# FPGA_MEMORIES.net
KiCad netlist of a schematic drawn in Altium Designer
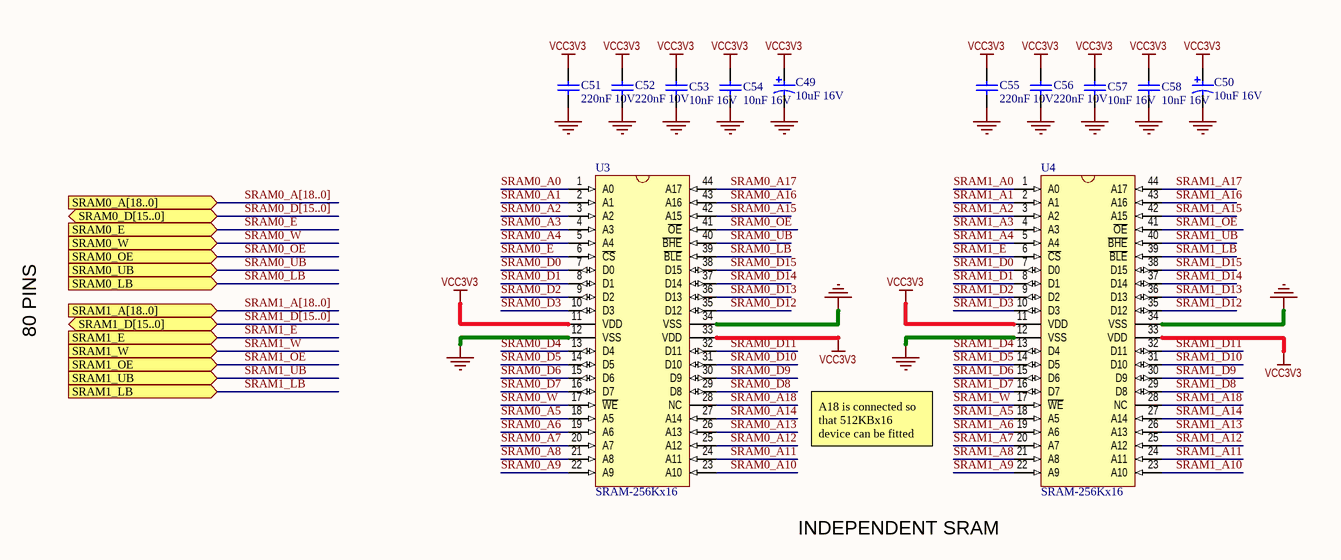
[diagram p0: FPGA_MEMORIES.SchDoc]

(export (version "E")
  (design (tool "Eeschema 10.0.6"))
  (components
    (comp (ref "C49")
      (value "10uF 16V")
      (footprint "CAPC3528")
      (description "Polar Capacitor")
      (libsource (lib "Altium Design Library") (part "CAP-P"))
    )
    (comp (ref "C50")
      (value "10uF 16V")
      (footprint "CAPC3528")
      (description "Polar Capacitor")
      (libsource (lib "Altium Design Library") (part "CAP-P"))
    )
    (comp (ref "C51")
      (value "220nF 10V")
      (footprint "CAPC1608")
      (description "Capacitor")
      (libsource (lib "Altium Design Library") (part "CAP-NP"))
    )
    (comp (ref "C52")
      (value "220nF 10V")
      (footprint "CAPC1608")
      (description "Capacitor")
      (libsource (lib "Altium Design Library") (part "CAP-NP"))
    )
    (comp (ref "C53")
      (value "10nF 16V")
      (footprint "CAPC1005")
      (description "Capacitor")
      (libsource (lib "Altium Design Library") (part "CAP-NP"))
    )
    (comp (ref "C54")
      (value "10nF 16V")
      (footprint "CAPC1005")
      (description "Capacitor")
      (libsource (lib "Altium Design Library") (part "CAP-NP"))
    )
    (comp (ref "C55")
      (value "220nF 10V")
      (footprint "CAPC1608")
      (description "Capacitor")
      (libsource (lib "Altium Design Library") (part "CAP-NP"))
    )
    (comp (ref "C56")
      (value "220nF 10V")
      (footprint "CAPC1608")
      (description "Capacitor")
      (libsource (lib "Altium Design Library") (part "CAP-NP"))
    )
    (comp (ref "C57")
      (value "10nF 16V")
      (footprint "CAPC1005")
      (description "Capacitor")
      (libsource (lib "Altium Design Library") (part "CAP-NP"))
    )
    (comp (ref "C58")
      (value "10nF 16V")
      (footprint "CAPC1005")
      (description "Capacitor")
      (libsource (lib "Altium Design Library") (part "CAP-NP"))
    )
    (comp (ref "U3")
      (value "SRAM-256Kx16")
      (footprint "TSOP80P1176-44")
      (description "256Kx16Bit SRAM TSOP44")
      (libsource (lib "Altium Design Library") (part "K6R4016V1D-T"))
    )
    (comp (ref "U4")
      (value "SRAM-256Kx16")
      (footprint "TSOP80P1176-44")
      (description "256Kx16Bit SRAM TSOP44")
      (libsource (lib "Altium Design Library") (part "K6R4016V1D-T"))
    )
  )
  (nets
    (net (code "1") (name "/SRAM0_A0") (class "Default")
      (node (ref "U3") (pin "1") (pinfunction "A0_1") (pintype "input"))
    )
    (net (code "2") (name "/SRAM0_A1") (class "Default")
      (node (ref "U3") (pin "2") (pinfunction "A1_2") (pintype "input"))
    )
    (net (code "3") (name "/SRAM0_A2") (class "Default")
      (node (ref "U3") (pin "3") (pinfunction "A2_3") (pintype "input"))
    )
    (net (code "4") (name "/SRAM0_A3") (class "Default")
      (node (ref "U3") (pin "4") (pinfunction "A3_4") (pintype "input"))
    )
    (net (code "5") (name "/SRAM0_A4") (class "Default")
      (node (ref "U3") (pin "5") (pinfunction "A4_5") (pintype "input"))
    )
    (net (code "6") (name "/SRAM0_A5") (class "Default")
      (node (ref "U3") (pin "18") (pinfunction "A5_18") (pintype "input"))
    )
    (net (code "7") (name "/SRAM0_A6") (class "Default")
      (node (ref "U3") (pin "19") (pinfunction "A6_19") (pintype "input"))
    )
    (net (code "8") (name "/SRAM0_A7") (class "Default")
      (node (ref "U3") (pin "20") (pinfunction "A7_20") (pintype "input"))
    )
    (net (code "9") (name "/SRAM0_A8") (class "Default")
      (node (ref "U3") (pin "21") (pinfunction "A8_21") (pintype "input"))
    )
    (net (code "10") (name "/SRAM0_A9") (class "Default")
      (node (ref "U3") (pin "22") (pinfunction "A9_22") (pintype "input"))
    )
    (net (code "11") (name "/SRAM0_A10") (class "Default")
      (node (ref "U3") (pin "23") (pinfunction "A10_23") (pintype "input"))
    )
    (net (code "12") (name "/SRAM0_A11") (class "Default")
      (node (ref "U3") (pin "24") (pinfunction "A11_24") (pintype "input"))
    )
    (net (code "13") (name "/SRAM0_A12") (class "Default")
      (node (ref "U3") (pin "25") (pinfunction "A12_25") (pintype "input"))
    )
    (net (code "14") (name "/SRAM0_A13") (class "Default")
      (node (ref "U3") (pin "26") (pinfunction "A13_26") (pintype "input"))
    )
    (net (code "15") (name "/SRAM0_A14") (class "Default")
      (node (ref "U3") (pin "27") (pinfunction "A14_27") (pintype "input"))
    )
    (net (code "16") (name "/SRAM0_A15") (class "Default")
      (node (ref "U3") (pin "42") (pinfunction "A15_42") (pintype "input"))
    )
    (net (code "17") (name "/SRAM0_A16") (class "Default")
      (node (ref "U3") (pin "43") (pinfunction "A16_43") (pintype "input"))
    )
    (net (code "18") (name "/SRAM0_A17") (class "Default")
      (node (ref "U3") (pin "44") (pinfunction "A17_44") (pintype "input"))
    )
    (net (code "19") (name "/SRAM0_A18") (class "Default")
      (node (ref "U3") (pin "28") (pinfunction "NC_28") (pintype "passive"))
    )
    (net (code "21") (name "/SRAM0_D0") (class "Default")
      (node (ref "U3") (pin "7") (pinfunction "D0_7") (pintype "bidirectional"))
    )
    (net (code "22") (name "/SRAM0_D1") (class "Default")
      (node (ref "U3") (pin "8") (pinfunction "D1_8") (pintype "bidirectional"))
    )
    (net (code "23") (name "/SRAM0_D2") (class "Default")
      (node (ref "U3") (pin "9") (pinfunction "D2_9") (pintype "bidirectional"))
    )
    (net (code "24") (name "/SRAM0_D3") (class "Default")
      (node (ref "U3") (pin "10") (pinfunction "D3_10") (pintype "bidirectional"))
    )
    (net (code "25") (name "/SRAM0_D4") (class "Default")
      (node (ref "U3") (pin "13") (pinfunction "D4_13") (pintype "bidirectional"))
    )
    (net (code "26") (name "/SRAM0_D5") (class "Default")
      (node (ref "U3") (pin "14") (pinfunction "D5_14") (pintype "bidirectional"))
    )
    (net (code "27") (name "/SRAM0_D6") (class "Default")
      (node (ref "U3") (pin "15") (pinfunction "D6_15") (pintype "bidirectional"))
    )
    (net (code "28") (name "/SRAM0_D7") (class "Default")
      (node (ref "U3") (pin "16") (pinfunction "D7_16") (pintype "bidirectional"))
    )
    (net (code "29") (name "/SRAM0_D8") (class "Default")
      (node (ref "U3") (pin "29") (pinfunction "D8_29") (pintype "bidirectional"))
    )
    (net (code "30") (name "/SRAM0_D9") (class "Default")
      (node (ref "U3") (pin "30") (pinfunction "D9_30") (pintype "bidirectional"))
    )
    (net (code "31") (name "/SRAM0_D10") (class "Default")
      (node (ref "U3") (pin "31") (pinfunction "D10_31") (pintype "bidirectional"))
    )
    (net (code "32") (name "/SRAM0_D11") (class "Default")
      (node (ref "U3") (pin "32") (pinfunction "D11_32") (pintype "bidirectional"))
    )
    (net (code "33") (name "/SRAM0_D12") (class "Default")
      (node (ref "U3") (pin "35") (pinfunction "D12_35") (pintype "bidirectional"))
    )
    (net (code "34") (name "/SRAM0_D13") (class "Default")
      (node (ref "U3") (pin "36") (pinfunction "D13_36") (pintype "bidirectional"))
    )
    (net (code "35") (name "/SRAM0_D14") (class "Default")
      (node (ref "U3") (pin "37") (pinfunction "D14_37") (pintype "bidirectional"))
    )
    (net (code "36") (name "/SRAM0_D15") (class "Default")
      (node (ref "U3") (pin "38") (pinfunction "D15_38") (pintype "bidirectional"))
    )
    (net (code "38") (name "/SRAM0_E") (class "Default")
      (node (ref "U3") (pin "6") (pinfunction "~{CS}_6") (pintype "input"))
    )
    (net (code "39") (name "/SRAM0_LB") (class "Default")
      (node (ref "U3") (pin "39") (pinfunction "~{BLE}_39") (pintype "input"))
    )
    (net (code "40") (name "/SRAM0_OE") (class "Default")
      (node (ref "U3") (pin "41") (pinfunction "~{OE}_41") (pintype "input"))
    )
    (net (code "41") (name "/SRAM0_UB") (class "Default")
      (node (ref "U3") (pin "40") (pinfunction "~{BHE}_40") (pintype "input"))
    )
    (net (code "42") (name "/SRAM0_W") (class "Default")
      (node (ref "U3") (pin "17") (pinfunction "~{WE}_17") (pintype "input"))
    )
    (net (code "43") (name "/SRAM1_A0") (class "Default")
      (node (ref "U4") (pin "1") (pinfunction "A0_1") (pintype "input"))
    )
    (net (code "44") (name "/SRAM1_A1") (class "Default")
      (node (ref "U4") (pin "2") (pinfunction "A1_2") (pintype "input"))
    )
    (net (code "45") (name "/SRAM1_A2") (class "Default")
      (node (ref "U4") (pin "3") (pinfunction "A2_3") (pintype "input"))
    )
    (net (code "46") (name "/SRAM1_A3") (class "Default")
      (node (ref "U4") (pin "4") (pinfunction "A3_4") (pintype "input"))
    )
    (net (code "47") (name "/SRAM1_A4") (class "Default")
      (node (ref "U4") (pin "5") (pinfunction "A4_5") (pintype "input"))
    )
    (net (code "48") (name "/SRAM1_A5") (class "Default")
      (node (ref "U4") (pin "18") (pinfunction "A5_18") (pintype "input"))
    )
    (net (code "49") (name "/SRAM1_A6") (class "Default")
      (node (ref "U4") (pin "19") (pinfunction "A6_19") (pintype "input"))
    )
    (net (code "50") (name "/SRAM1_A7") (class "Default")
      (node (ref "U4") (pin "20") (pinfunction "A7_20") (pintype "input"))
    )
    (net (code "51") (name "/SRAM1_A8") (class "Default")
      (node (ref "U4") (pin "21") (pinfunction "A8_21") (pintype "input"))
    )
    (net (code "52") (name "/SRAM1_A9") (class "Default")
      (node (ref "U4") (pin "22") (pinfunction "A9_22") (pintype "input"))
    )
    (net (code "53") (name "/SRAM1_A10") (class "Default")
      (node (ref "U4") (pin "23") (pinfunction "A10_23") (pintype "input"))
    )
    (net (code "54") (name "/SRAM1_A11") (class "Default")
      (node (ref "U4") (pin "24") (pinfunction "A11_24") (pintype "input"))
    )
    (net (code "55") (name "/SRAM1_A12") (class "Default")
      (node (ref "U4") (pin "25") (pinfunction "A12_25") (pintype "input"))
    )
    (net (code "56") (name "/SRAM1_A13") (class "Default")
      (node (ref "U4") (pin "26") (pinfunction "A13_26") (pintype "input"))
    )
    (net (code "57") (name "/SRAM1_A14") (class "Default")
      (node (ref "U4") (pin "27") (pinfunction "A14_27") (pintype "input"))
    )
    (net (code "58") (name "/SRAM1_A15") (class "Default")
      (node (ref "U4") (pin "42") (pinfunction "A15_42") (pintype "input"))
    )
    (net (code "59") (name "/SRAM1_A16") (class "Default")
      (node (ref "U4") (pin "43") (pinfunction "A16_43") (pintype "input"))
    )
    (net (code "60") (name "/SRAM1_A17") (class "Default")
      (node (ref "U4") (pin "44") (pinfunction "A17_44") (pintype "input"))
    )
    (net (code "61") (name "/SRAM1_A18") (class "Default")
      (node (ref "U4") (pin "28") (pinfunction "NC_28") (pintype "passive"))
    )
    (net (code "63") (name "/SRAM1_D0") (class "Default")
      (node (ref "U4") (pin "7") (pinfunction "D0_7") (pintype "bidirectional"))
    )
    (net (code "64") (name "/SRAM1_D1") (class "Default")
      (node (ref "U4") (pin "8") (pinfunction "D1_8") (pintype "bidirectional"))
    )
    (net (code "65") (name "/SRAM1_D2") (class "Default")
      (node (ref "U4") (pin "9") (pinfunction "D2_9") (pintype "bidirectional"))
    )
    (net (code "66") (name "/SRAM1_D3") (class "Default")
      (node (ref "U4") (pin "10") (pinfunction "D3_10") (pintype "bidirectional"))
    )
    (net (code "67") (name "/SRAM1_D4") (class "Default")
      (node (ref "U4") (pin "13") (pinfunction "D4_13") (pintype "bidirectional"))
    )
    (net (code "68") (name "/SRAM1_D5") (class "Default")
      (node (ref "U4") (pin "14") (pinfunction "D5_14") (pintype "bidirectional"))
    )
    (net (code "69") (name "/SRAM1_D6") (class "Default")
      (node (ref "U4") (pin "15") (pinfunction "D6_15") (pintype "bidirectional"))
    )
    (net (code "70") (name "/SRAM1_D7") (class "Default")
      (node (ref "U4") (pin "16") (pinfunction "D7_16") (pintype "bidirectional"))
    )
    (net (code "71") (name "/SRAM1_D8") (class "Default")
      (node (ref "U4") (pin "29") (pinfunction "D8_29") (pintype "bidirectional"))
    )
    (net (code "72") (name "/SRAM1_D9") (class "Default")
      (node (ref "U4") (pin "30") (pinfunction "D9_30") (pintype "bidirectional"))
    )
    (net (code "73") (name "/SRAM1_D10") (class "Default")
      (node (ref "U4") (pin "31") (pinfunction "D10_31") (pintype "bidirectional"))
    )
    (net (code "74") (name "/SRAM1_D11") (class "Default")
      (node (ref "U4") (pin "32") (pinfunction "D11_32") (pintype "bidirectional"))
    )
    (net (code "75") (name "/SRAM1_D12") (class "Default")
      (node (ref "U4") (pin "35") (pinfunction "D12_35") (pintype "bidirectional"))
    )
    (net (code "76") (name "/SRAM1_D13") (class "Default")
      (node (ref "U4") (pin "36") (pinfunction "D13_36") (pintype "bidirectional"))
    )
    (net (code "77") (name "/SRAM1_D14") (class "Default")
      (node (ref "U4") (pin "37") (pinfunction "D14_37") (pintype "bidirectional"))
    )
    (net (code "78") (name "/SRAM1_D15") (class "Default")
      (node (ref "U4") (pin "38") (pinfunction "D15_38") (pintype "bidirectional"))
    )
    (net (code "80") (name "/SRAM1_E") (class "Default")
      (node (ref "U4") (pin "6") (pinfunction "~{CS}_6") (pintype "input"))
    )
    (net (code "81") (name "/SRAM1_LB") (class "Default")
      (node (ref "U4") (pin "39") (pinfunction "~{BLE}_39") (pintype "input"))
    )
    (net (code "82") (name "/SRAM1_OE") (class "Default")
      (node (ref "U4") (pin "41") (pinfunction "~{OE}_41") (pintype "input"))
    )
    (net (code "83") (name "/SRAM1_UB") (class "Default")
      (node (ref "U4") (pin "40") (pinfunction "~{BHE}_40") (pintype "input"))
    )
    (net (code "84") (name "/SRAM1_W") (class "Default")
      (node (ref "U4") (pin "17") (pinfunction "~{WE}_17") (pintype "input"))
    )
    (net (code "85") (name "GND") (class "Default")
      (node (ref "C49") (pin "2") (pinfunction "2_2") (pintype "passive"))
      (node (ref "C50") (pin "2") (pinfunction "2_2") (pintype "passive"))
      (node (ref "C51") (pin "2") (pinfunction "2_2") (pintype "passive"))
      (node (ref "C52") (pin "2") (pinfunction "2_2") (pintype "passive"))
      (node (ref "C53") (pin "2") (pinfunction "2_2") (pintype "passive"))
      (node (ref "C54") (pin "2") (pinfunction "2_2") (pintype "passive"))
      (node (ref "C55") (pin "2") (pinfunction "2_2") (pintype "passive"))
      (node (ref "C56") (pin "2") (pinfunction "2_2") (pintype "passive"))
      (node (ref "C57") (pin "2") (pinfunction "2_2") (pintype "passive"))
      (node (ref "C58") (pin "2") (pinfunction "2_2") (pintype "passive"))
      (node (ref "U3") (pin "12") (pinfunction "VSS_12") (pintype "power_in"))
      (node (ref "U3") (pin "34") (pinfunction "VSS_34") (pintype "power_in"))
      (node (ref "U4") (pin "12") (pinfunction "VSS_12") (pintype "power_in"))
      (node (ref "U4") (pin "34") (pinfunction "VSS_34") (pintype "power_in"))
    )
    (net (code "86") (name "VCC3V3") (class "Default")
      (node (ref "C49") (pin "1") (pinfunction "1_1") (pintype "passive"))
      (node (ref "C50") (pin "1") (pinfunction "1_1") (pintype "passive"))
      (node (ref "C51") (pin "1") (pinfunction "1_1") (pintype "passive"))
      (node (ref "C52") (pin "1") (pinfunction "1_1") (pintype "passive"))
      (node (ref "C53") (pin "1") (pinfunction "1_1") (pintype "passive"))
      (node (ref "C54") (pin "1") (pinfunction "1_1") (pintype "passive"))
      (node (ref "C55") (pin "1") (pinfunction "1_1") (pintype "passive"))
      (node (ref "C56") (pin "1") (pinfunction "1_1") (pintype "passive"))
      (node (ref "C57") (pin "1") (pinfunction "1_1") (pintype "passive"))
      (node (ref "C58") (pin "1") (pinfunction "1_1") (pintype "passive"))
      (node (ref "U3") (pin "11") (pinfunction "VDD_11") (pintype "power_in"))
      (node (ref "U3") (pin "33") (pinfunction "VDD_33") (pintype "power_in"))
      (node (ref "U4") (pin "11") (pinfunction "VDD_11") (pintype "power_in"))
      (node (ref "U4") (pin "33") (pinfunction "VDD_33") (pintype "power_in"))
    )
  )
)
